# SmoothieboardGlcdAdapter2.net
KiCad netlist of a schematic drawn in EAGLE
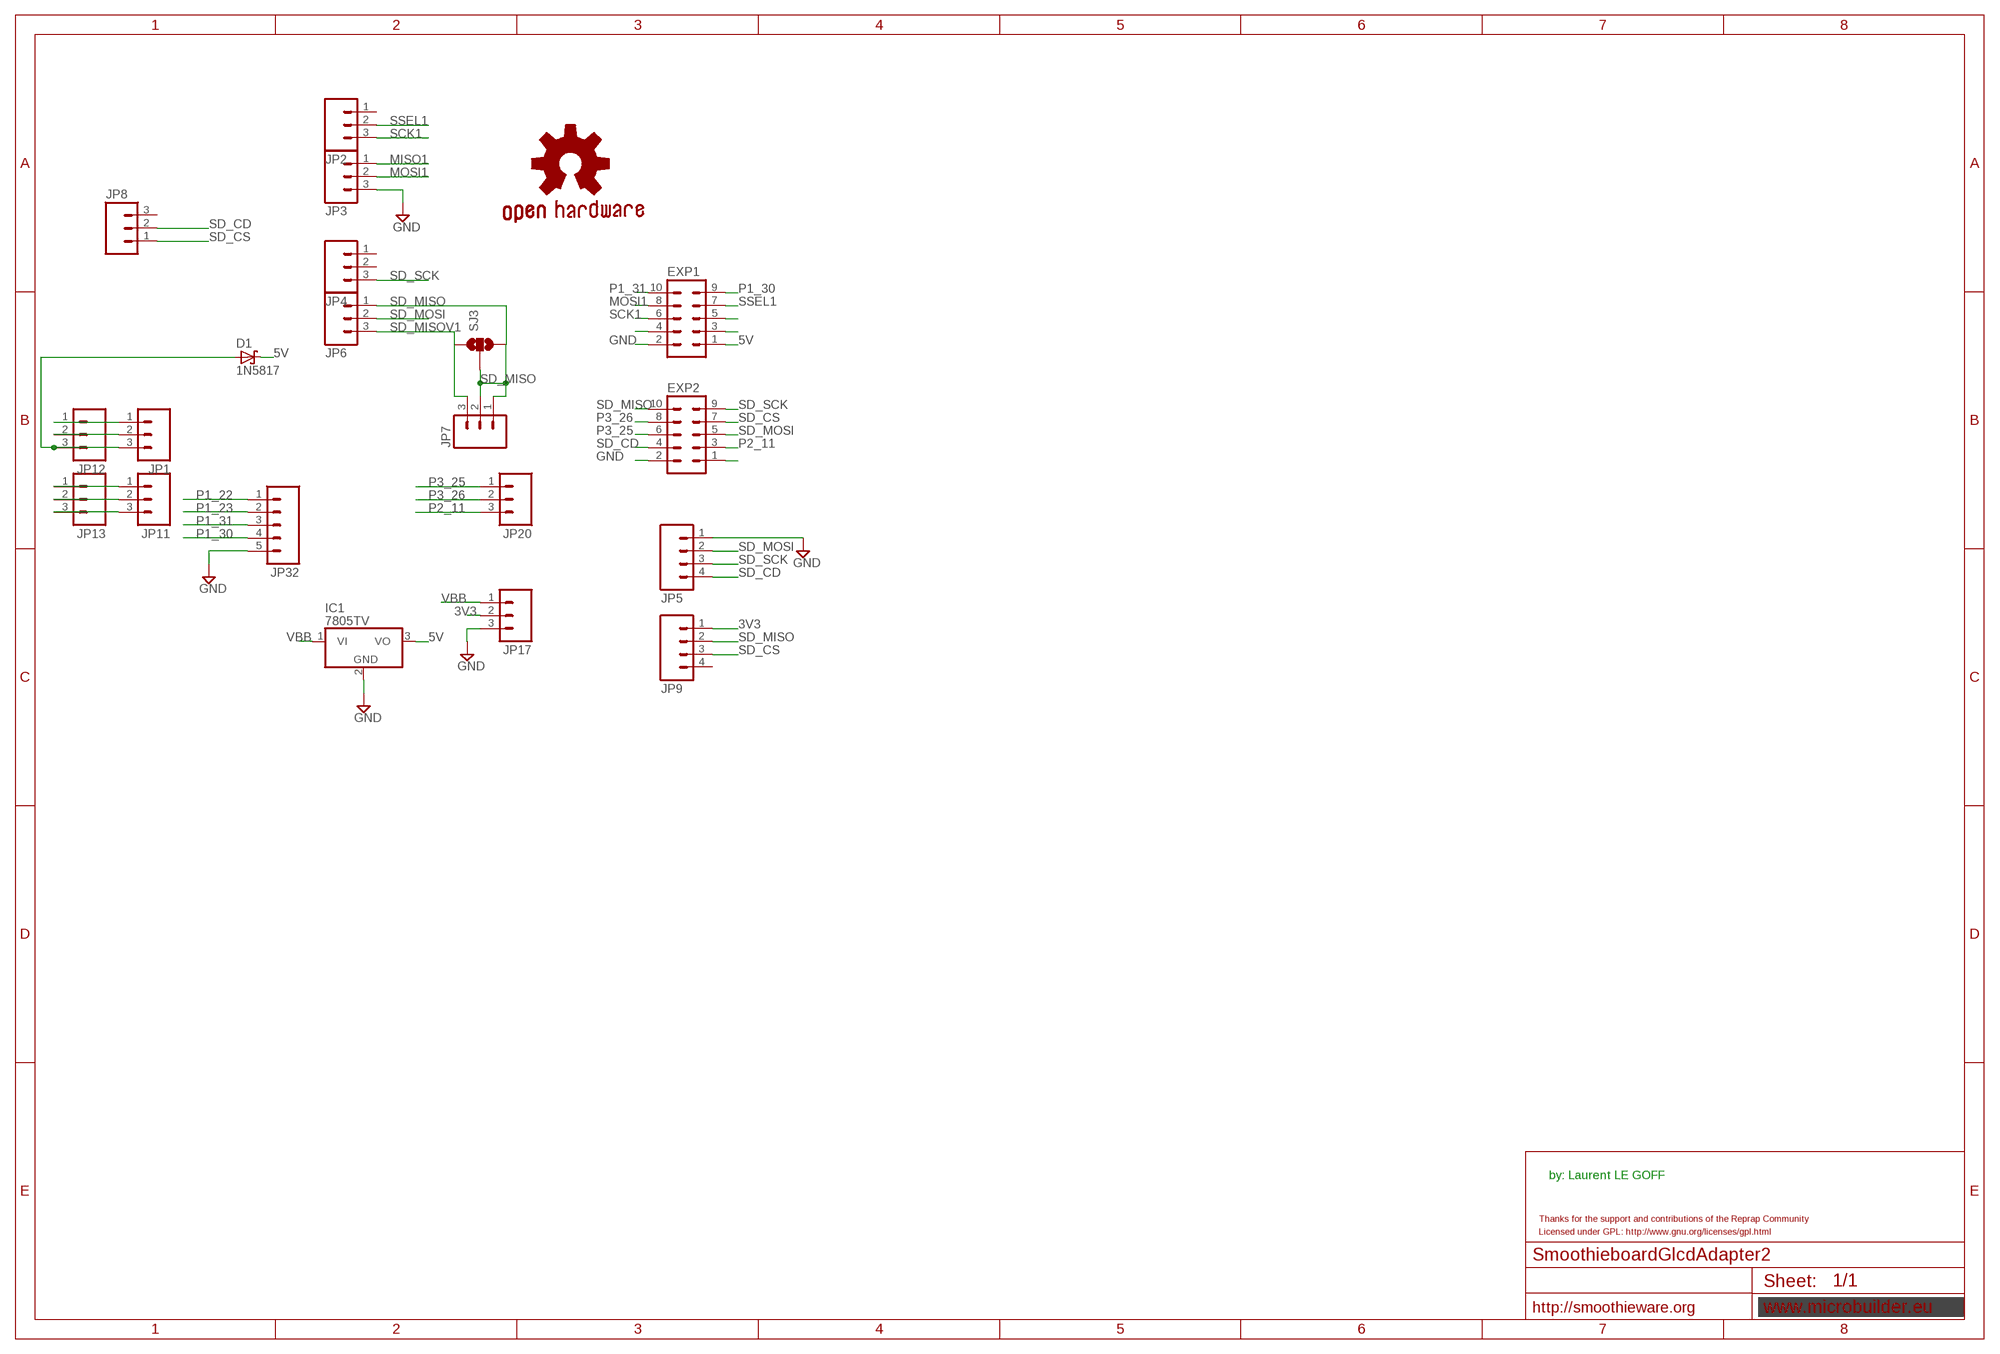
[diagram p0: schematic, sheet 1]

(export (version "E")
  (design (tool "Eeschema 10.0.6"))
  (components
    (comp (ref "D1")
      (value "1N5817")
      (footprint "eagle-import:DO41-7.6")
      (libsource (lib "eagle-import") (part "1N5817-B"))
    )
    (comp (ref "EXP1")
      (value "ML10")
      (footprint "eagle-import:ML10")
      (libsource (lib "eagle-import") (part "ML10"))
    )
    (comp (ref "EXP2")
      (value "ML10")
      (footprint "eagle-import:ML10")
      (libsource (lib "eagle-import") (part "ML10"))
    )
    (comp (ref "GOLD_ORB_SM1")
      (value "OSHWLOGO_GOLD_ORB_MED")
      (footprint "eagle-import:OSHW1")
      (libsource (lib "eagle-import") (part "OSHWLOGO_GOLD_ORB_MED"))
    )
    (comp (ref "IC1")
      (value "7805TV")
      (footprint "eagle-import:TO220V")
      (libsource (lib "eagle-import") (part "78TV05"))
    )
    (comp (ref "JP1")
      (value "M03PTH")
      (footprint "eagle-import:1X03")
      (libsource (lib "eagle-import") (part "M03PTH"))
    )
    (comp (ref "JP2")
      (value "M031X03_NO_SILK")
      (footprint "eagle-import:1X03_NO_SILK")
      (libsource (lib "eagle-import") (part "M031X03_NO_SILK"))
    )
    (comp (ref "JP3")
      (value "M031X03_NO_SILK")
      (footprint "eagle-import:1X03_NO_SILK")
      (libsource (lib "eagle-import") (part "M031X03_NO_SILK"))
    )
    (comp (ref "JP4")
      (value "M031X03_NO_SILK")
      (footprint "eagle-import:1X03_NO_SILK")
      (libsource (lib "eagle-import") (part "M031X03_NO_SILK"))
    )
    (comp (ref "JP5")
      (value "M041X04_NO_SILK")
      (footprint "eagle-import:1X04_NO_SILK")
      (libsource (lib "eagle-import") (part "M041X04_NO_SILK"))
    )
    (comp (ref "JP6")
      (value "M031X03_NO_SILK")
      (footprint "eagle-import:1X03_NO_SILK")
      (libsource (lib "eagle-import") (part "M031X03_NO_SILK"))
    )
    (comp (ref "JP7")
      (value "M03PTH")
      (footprint "eagle-import:1X03")
      (libsource (lib "eagle-import") (part "M03PTH"))
    )
    (comp (ref "JP8")
      (value "M03PTH")
      (footprint "eagle-import:1X03")
      (libsource (lib "eagle-import") (part "M03PTH"))
    )
    (comp (ref "JP9")
      (value "M041X04_NO_SILK")
      (footprint "eagle-import:1X04_NO_SILK")
      (libsource (lib "eagle-import") (part "M041X04_NO_SILK"))
    )
    (comp (ref "JP11")
      (value "M03PTH")
      (footprint "eagle-import:1X03")
      (libsource (lib "eagle-import") (part "M03PTH"))
    )
    (comp (ref "JP12")
      (value "M03PTH")
      (footprint "eagle-import:1X03")
      (libsource (lib "eagle-import") (part "M03PTH"))
    )
    (comp (ref "JP13")
      (value "M03PTH")
      (footprint "eagle-import:1X03")
      (libsource (lib "eagle-import") (part "M03PTH"))
    )
    (comp (ref "JP17")
      (value "M03PTH")
      (footprint "eagle-import:1X03")
      (libsource (lib "eagle-import") (part "M03PTH"))
    )
    (comp (ref "JP20")
      (value "M03PTH")
      (footprint "eagle-import:1X03")
      (libsource (lib "eagle-import") (part "M03PTH"))
    )
    (comp (ref "JP32")
      (value "M05PTH")
      (footprint "eagle-import:1X05")
      (libsource (lib "eagle-import") (part "M05PTH"))
    )
    (comp (ref "SJ3")
      (value "SOLDERJUMPER_2WAYS")
      (footprint "eagle-import:SJ_3")
      (libsource (lib "eagle-import") (part "SOLDERJUMPER_2WAYS"))
    )
  )
  (nets
    (net (code "1") (name "/3V3") (class "Default")
      (node (ref "JP17") (pin "2") (pinfunction "2_2") (pintype "passive"))
      (node (ref "JP9") (pin "1") (pinfunction "1_1") (pintype "passive"))
    )
    (net (code "2") (name "/5V") (class "Default")
      (node (ref "D1") (pin "C") (pinfunction "C_C") (pintype "passive"))
      (node (ref "EXP1") (pin "1") (pinfunction "1_1") (pintype "passive"))
      (node (ref "IC1") (pin "3") (pinfunction "VO_3") (pintype "passive"))
    )
    (net (code "3") (name "/MISO1") (class "Default")
      (node (ref "JP3") (pin "1") (pinfunction "1_1") (pintype "passive"))
    )
    (net (code "4") (name "/MOSI1") (class "Default")
      (node (ref "EXP1") (pin "8") (pinfunction "8_8") (pintype "passive"))
      (node (ref "JP3") (pin "2") (pinfunction "2_2") (pintype "passive"))
    )
    (net (code "5") (name "/P1_22") (class "Default")
      (node (ref "JP32") (pin "1") (pinfunction "1_1") (pintype "passive"))
    )
    (net (code "6") (name "/P1_23") (class "Default")
      (node (ref "JP32") (pin "2") (pinfunction "2_2") (pintype "passive"))
    )
    (net (code "7") (name "/P1_30") (class "Default")
      (node (ref "EXP1") (pin "9") (pinfunction "9_9") (pintype "passive"))
      (node (ref "JP32") (pin "4") (pinfunction "4_4") (pintype "passive"))
    )
    (net (code "8") (name "/P1_31") (class "Default")
      (node (ref "EXP1") (pin "10") (pinfunction "10_10") (pintype "passive"))
      (node (ref "JP32") (pin "3") (pinfunction "3_3") (pintype "passive"))
    )
    (net (code "9") (name "/P2_11") (class "Default")
      (node (ref "EXP2") (pin "3") (pinfunction "3_3") (pintype "passive"))
      (node (ref "JP20") (pin "3") (pinfunction "3_3") (pintype "passive"))
    )
    (net (code "10") (name "/P3_25") (class "Default")
      (node (ref "EXP2") (pin "6") (pinfunction "6_6") (pintype "passive"))
      (node (ref "JP20") (pin "1") (pinfunction "1_1") (pintype "passive"))
    )
    (net (code "11") (name "/P3_26") (class "Default")
      (node (ref "EXP2") (pin "8") (pinfunction "8_8") (pintype "passive"))
      (node (ref "JP20") (pin "2") (pinfunction "2_2") (pintype "passive"))
    )
    (net (code "12") (name "/SCK1") (class "Default")
      (node (ref "EXP1") (pin "6") (pinfunction "6_6") (pintype "passive"))
      (node (ref "JP2") (pin "3") (pinfunction "3_3") (pintype "passive"))
    )
    (net (code "13") (name "/SD_CD") (class "Default")
      (node (ref "EXP2") (pin "4") (pinfunction "4_4") (pintype "passive"))
      (node (ref "JP5") (pin "4") (pinfunction "4_4") (pintype "passive"))
      (node (ref "JP8") (pin "2") (pinfunction "2_2") (pintype "passive"))
    )
    (net (code "14") (name "/SD_CS") (class "Default")
      (node (ref "EXP2") (pin "7") (pinfunction "7_7") (pintype "passive"))
      (node (ref "JP8") (pin "1") (pinfunction "1_1") (pintype "passive"))
      (node (ref "JP9") (pin "3") (pinfunction "3_3") (pintype "passive"))
    )
    (net (code "15") (name "/SD_MISO") (class "Default")
      (node (ref "EXP2") (pin "10") (pinfunction "10_10") (pintype "passive"))
      (node (ref "JP6") (pin "1") (pinfunction "1_1") (pintype "passive"))
      (node (ref "JP7") (pin "1") (pinfunction "1_1") (pintype "passive"))
      (node (ref "JP7") (pin "2") (pinfunction "2_2") (pintype "passive"))
      (node (ref "JP9") (pin "2") (pinfunction "2_2") (pintype "passive"))
      (node (ref "SJ3") (pin "2") (pinfunction "2_2") (pintype "passive"))
      (node (ref "SJ3") (pin "3") (pinfunction "3_3") (pintype "passive"))
    )
    (net (code "16") (name "/SD_MISOV1") (class "Default")
      (node (ref "JP6") (pin "3") (pinfunction "3_3") (pintype "passive"))
      (node (ref "JP7") (pin "3") (pinfunction "3_3") (pintype "passive"))
      (node (ref "SJ3") (pin "1") (pinfunction "1_1") (pintype "passive"))
    )
    (net (code "17") (name "/SD_MOSI") (class "Default")
      (node (ref "EXP2") (pin "5") (pinfunction "5_5") (pintype "passive"))
      (node (ref "JP5") (pin "2") (pinfunction "2_2") (pintype "passive"))
      (node (ref "JP6") (pin "2") (pinfunction "2_2") (pintype "passive"))
    )
    (net (code "18") (name "/SD_SCK") (class "Default")
      (node (ref "EXP2") (pin "9") (pinfunction "9_9") (pintype "passive"))
      (node (ref "JP4") (pin "3") (pinfunction "3_3") (pintype "passive"))
      (node (ref "JP5") (pin "3") (pinfunction "3_3") (pintype "passive"))
    )
    (net (code "19") (name "/SSEL1") (class "Default")
      (node (ref "EXP1") (pin "7") (pinfunction "7_7") (pintype "passive"))
      (node (ref "JP2") (pin "2") (pinfunction "2_2") (pintype "passive"))
    )
    (net (code "20") (name "/VBB") (class "Default")
      (node (ref "IC1") (pin "1") (pinfunction "VI_1") (pintype "input"))
      (node (ref "JP17") (pin "1") (pinfunction "1_1") (pintype "passive"))
    )
    (net (code "21") (name "GND") (class "Default")
      (node (ref "EXP1") (pin "2") (pinfunction "2_2") (pintype "passive"))
      (node (ref "EXP2") (pin "2") (pinfunction "2_2") (pintype "passive"))
      (node (ref "IC1") (pin "2") (pinfunction "GND_2") (pintype "passive"))
      (node (ref "JP17") (pin "3") (pinfunction "3_3") (pintype "passive"))
      (node (ref "JP3") (pin "3") (pinfunction "3_3") (pintype "passive"))
      (node (ref "JP32") (pin "5") (pinfunction "5_5") (pintype "passive"))
      (node (ref "JP5") (pin "1") (pinfunction "1_1") (pintype "passive"))
    )
    (net (code "22") (name "Net-(D1-PadA)") (class "Default")
      (node (ref "D1") (pin "A") (pinfunction "A_A") (pintype "passive"))
      (node (ref "JP1") (pin "3") (pinfunction "3_3") (pintype "passive"))
      (node (ref "JP12") (pin "3") (pinfunction "3_3") (pintype "passive"))
    )
    (net (code "23") (name "Net-(JP1-Pad1)") (class "Default")
      (node (ref "JP1") (pin "1") (pinfunction "1_1") (pintype "passive"))
      (node (ref "JP12") (pin "1") (pinfunction "1_1") (pintype "passive"))
    )
    (net (code "24") (name "Net-(JP1-Pad2)") (class "Default")
      (node (ref "JP1") (pin "2") (pinfunction "2_2") (pintype "passive"))
      (node (ref "JP12") (pin "2") (pinfunction "2_2") (pintype "passive"))
    )
    (net (code "25") (name "Net-(JP11-Pad1)") (class "Default")
      (node (ref "JP11") (pin "1") (pinfunction "1_1") (pintype "passive"))
      (node (ref "JP13") (pin "1") (pinfunction "1_1") (pintype "passive"))
    )
    (net (code "26") (name "Net-(JP11-Pad2)") (class "Default")
      (node (ref "JP11") (pin "2") (pinfunction "2_2") (pintype "passive"))
      (node (ref "JP13") (pin "2") (pinfunction "2_2") (pintype "passive"))
    )
    (net (code "27") (name "Net-(JP11-Pad3)") (class "Default")
      (node (ref "JP11") (pin "3") (pinfunction "3_3") (pintype "passive"))
      (node (ref "JP13") (pin "3") (pinfunction "3_3") (pintype "passive"))
    )
    (net (code "28") (name "unconnected-(EXP1-Pad3)") (class "Default")
      (node (ref "EXP1") (pin "3") (pinfunction "3_3") (pintype "passive"))
    )
    (net (code "29") (name "unconnected-(EXP1-Pad4)") (class "Default")
      (node (ref "EXP1") (pin "4") (pinfunction "4_4") (pintype "passive"))
    )
    (net (code "30") (name "unconnected-(EXP1-Pad5)") (class "Default")
      (node (ref "EXP1") (pin "5") (pinfunction "5_5") (pintype "passive"))
    )
    (net (code "31") (name "unconnected-(EXP2-Pad1)") (class "Default")
      (node (ref "EXP2") (pin "1") (pinfunction "1_1") (pintype "passive"))
    )
    (net (code "32") (name "unconnected-(JP2-Pad1)") (class "Default")
      (node (ref "JP2") (pin "1") (pinfunction "1_1") (pintype "passive"))
    )
    (net (code "33") (name "unconnected-(JP4-Pad1)") (class "Default")
      (node (ref "JP4") (pin "1") (pinfunction "1_1") (pintype "passive"))
    )
    (net (code "34") (name "unconnected-(JP4-Pad2)") (class "Default")
      (node (ref "JP4") (pin "2") (pinfunction "2_2") (pintype "passive"))
    )
    (net (code "35") (name "unconnected-(JP8-Pad3)") (class "Default")
      (node (ref "JP8") (pin "3") (pinfunction "3_3") (pintype "passive"))
    )
    (net (code "36") (name "unconnected-(JP9-Pad4)") (class "Default")
      (node (ref "JP9") (pin "4") (pinfunction "4_4") (pintype "passive"))
    )
  )
)
